# Quasar_ARM.net
KiCad netlist of a schematic drawn in Altium Designer
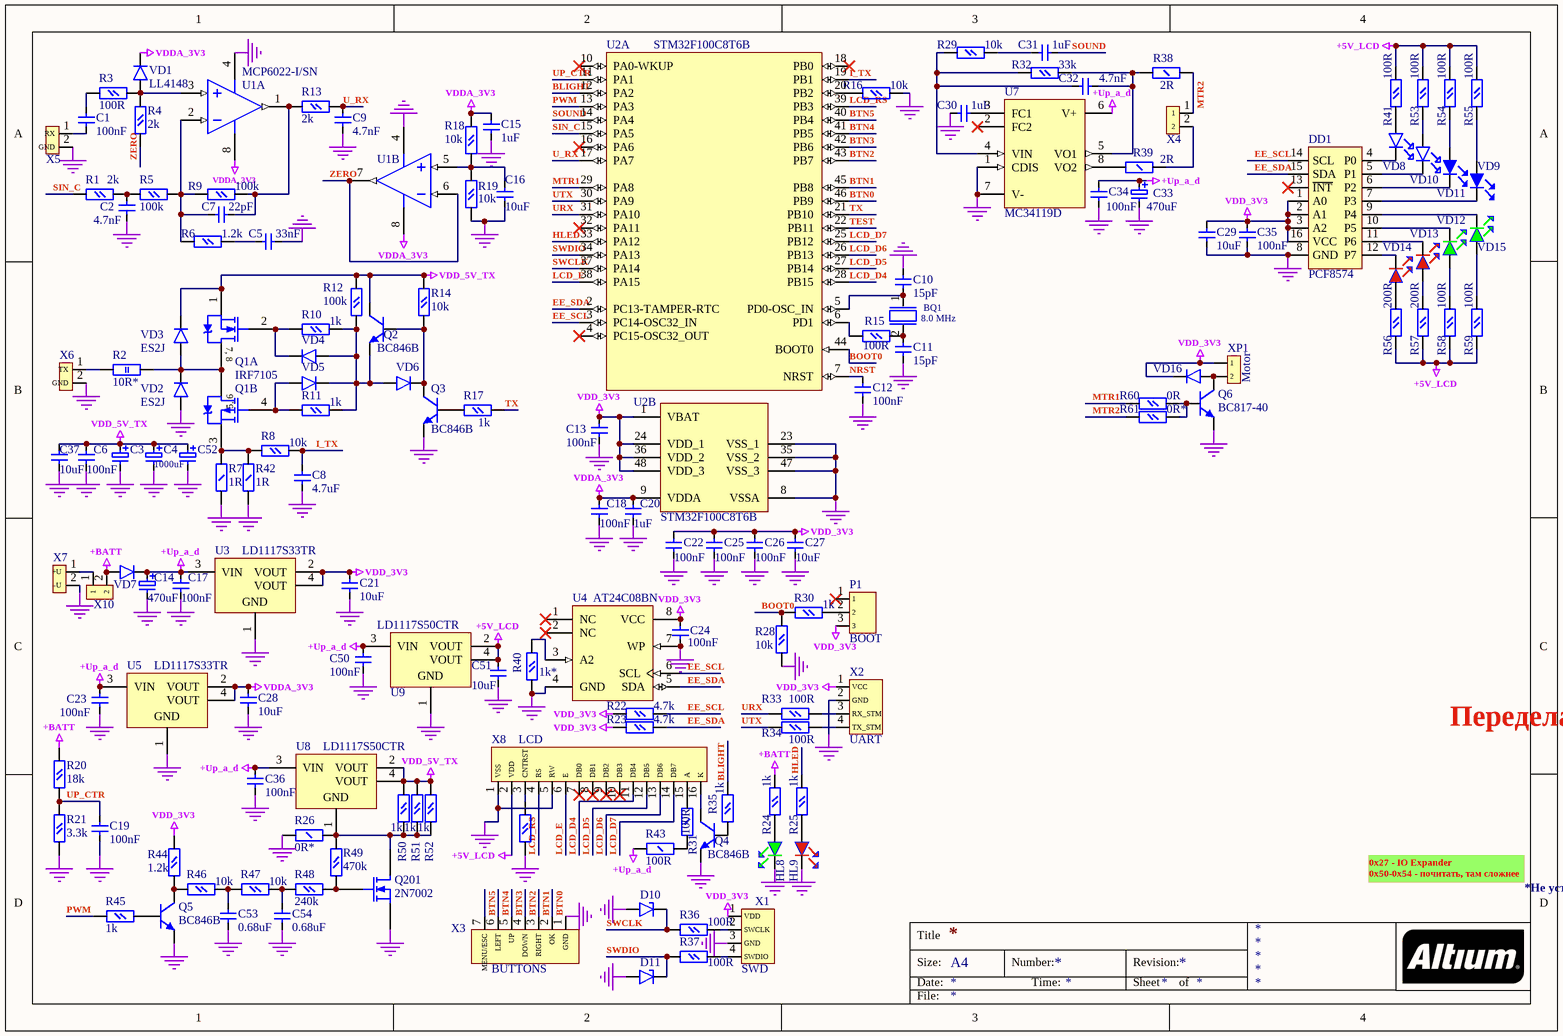
[diagram p0: Quasar_ARM_схема.SchDoc]

(export (version "E")
  (design (tool "Eeschema 10.0.6"))
  (components
    (comp (ref "BQ1")
      (value "8.0 MHz")
      (footprint "Quartz_SMD_2pin")
      (libsource (lib "AS") (part "Quartz_2pin"))
    )
    (comp (ref "C1")
      (value "100nF")
      (footprint "0603_CAP_0.9_CL10A")
      (description "Capacitor_0603")
      (libsource (lib "AS") (part "CAP_0603"))
    )
    (comp (ref "C2")
      (value "4.7nF")
      (footprint "0603_CAP_0.9_CL10A")
      (description "Capacitor_0603")
      (libsource (lib "AS") (part "CAP_0603"))
    )
    (comp (ref "C3")
      (value "1000uF")
      (footprint "CAP-D")
      (description "Capacitor case D")
      (libsource (lib "AS") (part "CAP_D"))
    )
    (comp (ref "C4")
      (value "1000uF")
      (footprint "CAP-D")
      (description "Capacitor case D")
      (libsource (lib "AS") (part "CAP_D"))
    )
    (comp (ref "C5")
      (value "33nF")
      (footprint "0603_CAP_0.9_CL10A")
      (description "Capacitor_0603")
      (libsource (lib "AS") (part "CAP_0603"))
    )
    (comp (ref "C6")
      (value "100nF")
      (footprint "0603_CAP_0.9_CL10A")
      (description "Capacitor_0603")
      (libsource (lib "AS") (part "CAP_0603"))
    )
    (comp (ref "C7")
      (value "22pF")
      (footprint "0603_CAP_0.9_CL10A")
      (description "Capacitor_0603")
      (libsource (lib "AS") (part "CAP_0603"))
    )
    (comp (ref "C8")
      (value "4.7uF")
      (footprint "0603_CAP_0.9_CL10A")
      (description "Capacitor_0603")
      (libsource (lib "AS") (part "CAP_0603"))
    )
    (comp (ref "C9")
      (value "4.7nF")
      (footprint "0603_CAP_0.9_CL10A")
      (description "Capacitor_0603")
      (libsource (lib "AS") (part "CAP_0603"))
    )
    (comp (ref "C10")
      (value "15pF")
      (footprint "0603_CAP_0.9_CL10A")
      (description "Capacitor_0603")
      (libsource (lib "AS") (part "CAP_0603"))
    )
    (comp (ref "C11")
      (value "15pF")
      (footprint "0603_CAP_0.9_CL10A")
      (description "Capacitor_0603")
      (libsource (lib "AS") (part "CAP_0603"))
    )
    (comp (ref "C12")
      (value "100nF")
      (footprint "0603_CAP_0.9_CL10A")
      (description "Capacitor_0603")
      (libsource (lib "AS") (part "CAP_0603"))
    )
    (comp (ref "C13")
      (value "100nF")
      (footprint "0603_CAP_0.9_CL10A")
      (description "Capacitor_0603")
      (libsource (lib "AS") (part "CAP_0603"))
    )
    (comp (ref "C14")
      (value "470uF")
      (footprint "CAP-D")
      (description "Capacitor case D")
      (libsource (lib "AS") (part "CAP_D"))
    )
    (comp (ref "C15")
      (value "1uF")
      (footprint "0603_CAP_0.9_CL10A")
      (description "Capacitor_0603")
      (libsource (lib "AS") (part "CAP_0603"))
    )
    (comp (ref "C16")
      (value "10uF")
      (footprint "1206_C_1.8_CL31B")
      (description "Capacitor_1206")
      (libsource (lib "AS") (part "CAP_1206"))
    )
    (comp (ref "C17")
      (value "100nF")
      (footprint "0603_CAP_0.9_CL10A")
      (description "Capacitor_0603")
      (libsource (lib "AS") (part "CAP_0603"))
    )
    (comp (ref "C18")
      (value "100nF")
      (footprint "0603_CAP_0.9_CL10A")
      (description "Capacitor_0603")
      (libsource (lib "AS") (part "CAP_0603"))
    )
    (comp (ref "C19")
      (value "100nF")
      (footprint "0603_CAP_0.9_CL10A")
      (description "Capacitor_0603")
      (libsource (lib "AS") (part "CAP_0603"))
    )
    (comp (ref "C20")
      (value "1uF")
      (footprint "0603_CAP_0.9_CL10A")
      (description "Capacitor_0603")
      (libsource (lib "AS") (part "CAP_0603"))
    )
    (comp (ref "C21")
      (value "10uF")
      (footprint "1206_C_1.8_CL31B")
      (description "Capacitor_1206")
      (libsource (lib "AS") (part "CAP_1206"))
    )
    (comp (ref "C22")
      (value "100nF")
      (footprint "0603_CAP_0.9_CL10A")
      (description "Capacitor_0603")
      (libsource (lib "AS") (part "CAP_0603"))
    )
    (comp (ref "C23")
      (value "100nF")
      (footprint "0603_CAP_0.9_CL10A")
      (description "Capacitor_0603")
      (libsource (lib "AS") (part "CAP_0603"))
    )
    (comp (ref "C24")
      (value "100nF")
      (footprint "0603_CAP_0.9_CL10A")
      (description "Capacitor_0603")
      (libsource (lib "AS") (part "CAP_0603"))
    )
    (comp (ref "C25")
      (value "100nF")
      (footprint "0603_CAP_0.9_CL10A")
      (description "Capacitor_0603")
      (libsource (lib "AS") (part "CAP_0603"))
    )
    (comp (ref "C26")
      (value "100nF")
      (footprint "0603_CAP_0.9_CL10A")
      (description "Capacitor_0603")
      (libsource (lib "AS") (part "CAP_0603"))
    )
    (comp (ref "C27")
      (value "10uF")
      (footprint "1206_C_1.8_CL31B")
      (description "Capacitor_1206")
      (libsource (lib "AS") (part "CAP_1206"))
    )
    (comp (ref "C28")
      (value "10uF")
      (footprint "1206_C_1.8_CL31B")
      (description "Capacitor_1206")
      (libsource (lib "AS") (part "CAP_1206"))
    )
    (comp (ref "C29")
      (value "10uF")
      (footprint "1206_C_1.8_CL31B")
      (description "Capacitor_1206")
      (libsource (lib "AS") (part "CAP_1206"))
    )
    (comp (ref "C30")
      (value "1uF")
      (footprint "0603_CAP_0.9_CL10A")
      (description "Capacitor_0603")
      (libsource (lib "AS") (part "CAP_0603"))
    )
    (comp (ref "C31")
      (value "1uF")
      (footprint "0603_CAP_0.9_CL10A")
      (description "Capacitor_0603")
      (libsource (lib "AS") (part "CAP_0603"))
    )
    (comp (ref "C32")
      (value "4.7nF")
      (footprint "0603_CAP_0.9_CL10A")
      (description "Capacitor_0603")
      (libsource (lib "AS") (part "CAP_0603"))
    )
    (comp (ref "C33")
      (value "470uF")
      (footprint "CAP-D")
      (description "Capacitor case D")
      (libsource (lib "AS") (part "CAP_D"))
    )
    (comp (ref "C34")
      (value "100nF")
      (footprint "0603_CAP_0.9_CL10A")
      (description "Capacitor_0603")
      (libsource (lib "AS") (part "CAP_0603"))
    )
    (comp (ref "C35")
      (value "100nF")
      (footprint "0603_CAP_0.9_CL10A")
      (description "Capacitor_0603")
      (libsource (lib "AS") (part "CAP_0603"))
    )
    (comp (ref "C36")
      (value "100nF")
      (footprint "0603_CAP_0.9_CL10A")
      (description "Capacitor_0603")
      (libsource (lib "AS") (part "CAP_0603"))
    )
    (comp (ref "C37")
      (value "10uF")
      (footprint "1206_C_1.8_CL31B")
      (description "Capacitor_1206")
      (libsource (lib "AS") (part "CAP_1206"))
    )
    (comp (ref "C50")
      (value "100nF")
      (footprint "0603_CAP_0.9_CL10A")
      (description "Capacitor_0603")
      (libsource (lib "AS") (part "CAP_0603"))
    )
    (comp (ref "C51")
      (value "10uF")
      (footprint "1206_C_1.8_CL31B")
      (description "Capacitor_1206")
      (libsource (lib "AS") (part "CAP_1206"))
    )
    (comp (ref "C52")
      (value "1000uF")
      (footprint "CAP-D")
      (description "Capacitor case D")
      (libsource (lib "AS") (part "CAP_D"))
    )
    (comp (ref "C53")
      (value "0.68uF")
      (footprint "0603_CAP_0.9_CL10A")
      (description "Capacitor_0603")
      (libsource (lib "AS") (part "CAP_0603"))
    )
    (comp (ref "C54")
      (value "0.68uF")
      (footprint "0603_CAP_0.9_CL10A")
      (description "Capacitor_0603")
      (libsource (lib "AS") (part "CAP_0603"))
    )
    (comp (ref "D10")
      (value "BZX384-C5V1")
      (footprint "0402")
      (description "Diode Zener")
      (libsource (lib "AS") (part "Diode_Zener1"))
    )
    (comp (ref "D11")
      (value "BZX384-C5V1")
      (footprint "0402")
      (description "Diode Zener")
      (libsource (lib "AS") (part "Diode_Zener1"))
    )
    (comp (ref "DD1")
      (value "PCF8574")
      (footprint "SOIC127P1030X265-16N")
      (description "I/O Expander")
      (libsource (lib "AS") (part "PCF8574"))
    )
    (comp (ref "HL8")
      (value "GNL-0603GC")
      (footprint "0603")
      (description "0402-0603-1206")
      (libsource (lib "") (part "LED_GREEN_1"))
    )
    (comp (ref "HL9")
      (value "KT-SMD0603-R")
      (footprint "1206")
      (description "0402-0603-1206")
      (libsource (lib "") (part "LED_RED_1"))
    )
    (comp (ref "P1")
      (value "BOOT")
      (footprint "3pin(2.54mm)")
      (libsource (lib "AS") (part "Connector - 3 pin_1"))
    )
    (comp (ref "Q1")
      (value "IRF7105")
      (footprint "SO-8_N")
      (description "HEXFET Power MOSFET")
      (fields (field (name "PUBLISHER") "Altium Limited"))
      (libsource (lib "IR Discrete MOSFET - Power") (part "IRF7105"))
    )
    (comp (ref "Q2")
      (value "BC846B")
      (footprint "SOT-416")
      (description "NPN General-purpose Transistor")
      (libsource (lib "AS") (part "Transistor_NPN"))
    )
    (comp (ref "Q3")
      (value "BC846B")
      (footprint "SOT-416")
      (description "NPN General-purpose Transistor")
      (libsource (lib "AS") (part "Transistor_NPN"))
    )
    (comp (ref "Q4")
      (value "BC846B")
      (footprint "SOT-416")
      (description "NPN General-purpose Transistor")
      (libsource (lib "AS") (part "Transistor_NPN"))
    )
    (comp (ref "Q5")
      (value "BC846B")
      (footprint "SOT-416")
      (description "NPN General-purpose Transistor")
      (libsource (lib "AS") (part "Transistor_NPN"))
    )
    (comp (ref "Q6")
      (value "BC817-40")
      (footprint "SOT-416")
      (description "NPN General-purpose Transistor")
      (libsource (lib "AS") (part "Transistor_NPN"))
    )
    (comp (ref "Q201")
      (value "2N7002")
      (footprint "SOT23")
      (description "N-Channel Enhancement Mode Vertical DMOS FET")
      (fields (field (name "PUBLISHER") "Altium Limited"))
      (libsource (lib "Zetex Discrete MOSFET") (part "2N7002"))
    )
    (comp (ref "R1")
      (value "2k")
      (footprint "0603_R")
      (description "0603")
      (libsource (lib "AS") (part "RES_0603_0.125W"))
    )
    (comp (ref "R2")
      (value "10R*")
      (footprint "R_THT_2W_9x3.2x12.7")
      (description "Res THT")
      (libsource (lib "AS") (part "RES_THT_2W"))
    )
    (comp (ref "R3")
      (value "100R")
      (footprint "0603_R")
      (description "0603")
      (libsource (lib "AS") (part "RES_0603_0.1W"))
    )
    (comp (ref "R4")
      (value "2k")
      (footprint "0603_R")
      (description "0603")
      (libsource (lib "AS") (part "RES_0603_0.125W"))
    )
    (comp (ref "R5")
      (value "100k")
      (footprint "0603_R")
      (description "0603")
      (libsource (lib "AS") (part "RES_0603_0.125W"))
    )
    (comp (ref "R6")
      (value "1.2k")
      (footprint "0603_R")
      (description "0603")
      (libsource (lib "AS") (part "RES_0603_0.125W"))
    )
    (comp (ref "R7")
      (value "1R")
      (footprint "1206_R")
      (description "1206")
      (libsource (lib "AS") (part "RES_1206_0.25W"))
    )
    (comp (ref "R8")
      (value "10k")
      (footprint "0603_R")
      (description "0603")
      (libsource (lib "AS") (part "RES_0603_0.125W"))
    )
    (comp (ref "R9")
      (value "100k")
      (footprint "0603_R")
      (description "0603")
      (libsource (lib "AS") (part "RES_0603_0.125W"))
    )
    (comp (ref "R10")
      (value "1k")
      (footprint "0603_R")
      (description "0603")
      (libsource (lib "AS") (part "RES_0603_0.125W"))
    )
    (comp (ref "R11")
      (value "1k")
      (footprint "0603_R")
      (description "0603")
      (libsource (lib "AS") (part "RES_0603_0.125W"))
    )
    (comp (ref "R12")
      (value "100k")
      (footprint "0603_R")
      (description "0603")
      (libsource (lib "AS") (part "RES_0603_0.125W"))
    )
    (comp (ref "R13")
      (value "2k")
      (footprint "0603_R")
      (description "0603")
      (libsource (lib "AS") (part "RES_0603_0.125W"))
    )
    (comp (ref "R14")
      (value "10k")
      (footprint "0603_R")
      (description "0603")
      (libsource (lib "AS") (part "RES_0603_0.125W"))
    )
    (comp (ref "R15")
      (value "100R")
      (footprint "0603_R")
      (description "0603")
      (libsource (lib "AS") (part "RES_0603_0.1W"))
    )
    (comp (ref "R16")
      (value "10k")
      (footprint "0603_R")
      (description "0603")
      (libsource (lib "AS") (part "RES_0603_0.125W"))
    )
    (comp (ref "R17")
      (value "1k")
      (footprint "0603_R")
      (description "0603")
      (libsource (lib "AS") (part "RES_0603_0.125W"))
    )
    (comp (ref "R18")
      (value "10k")
      (footprint "0603_R")
      (description "0603")
      (libsource (lib "AS") (part "RES_0603_0.125W"))
    )
    (comp (ref "R19")
      (value "10k")
      (footprint "0603_R")
      (description "0603")
      (libsource (lib "AS") (part "RES_0603_0.125W"))
    )
    (comp (ref "R20")
      (value "18k")
      (footprint "0603_R")
      (description "0603")
      (libsource (lib "AS") (part "RES_0603_0.125W"))
    )
    (comp (ref "R21")
      (value "3.3k")
      (footprint "0603_R")
      (description "0603")
      (libsource (lib "AS") (part "RES_0603_0.125W"))
    )
    (comp (ref "R22")
      (value "4.7k")
      (footprint "0603_R")
      (description "0603")
      (libsource (lib "AS") (part "RES_0603_0.125W"))
    )
    (comp (ref "R23")
      (value "4.7k")
      (footprint "0603_R")
      (description "0603")
      (libsource (lib "AS") (part "RES_0603_0.125W"))
    )
    (comp (ref "R24")
      (value "1k")
      (footprint "0603_R")
      (description "0603")
      (libsource (lib "AS") (part "RES_0603_0.125W"))
    )
    (comp (ref "R25")
      (value "1k")
      (footprint "0603_R")
      (description "0603")
      (libsource (lib "AS") (part "RES_0603_0.125W"))
    )
    (comp (ref "R26")
      (value "0R*")
      (footprint "1206_R")
      (description "1206")
      (libsource (lib "AS") (part "RES_1206_0.25W"))
    )
    (comp (ref "R27")
      (value "10k-contrast")
      (footprint "0603_R")
      (description "0603")
      (libsource (lib "AS") (part "RES_0603_0.125W"))
    )
    (comp (ref "R28")
      (value "10k")
      (footprint "0603_R")
      (description "0603")
      (libsource (lib "AS") (part "RES_0603_0.125W"))
    )
    (comp (ref "R29")
      (value "10k")
      (footprint "0603_R")
      (description "0603")
      (libsource (lib "AS") (part "RES_0603_0.125W"))
    )
    (comp (ref "R30")
      (value "1k")
      (footprint "0603_R")
      (description "0603")
      (libsource (lib "AS") (part "RES_0603_0.125W"))
    )
    (comp (ref "R31")
      (value "100R")
      (footprint "1206_R")
      (description "1206")
      (libsource (lib "AS") (part "RES_1206_0.25W"))
    )
    (comp (ref "R32")
      (value "33k")
      (footprint "0603_R")
      (description "0603")
      (libsource (lib "AS") (part "RES_0603_0.125W"))
    )
    (comp (ref "R33")
      (value "100R")
      (footprint "0603_R")
      (description "0603")
      (libsource (lib "AS") (part "RES_0603_0.1W"))
    )
    (comp (ref "R34")
      (value "100R")
      (footprint "0603_R")
      (description "0603")
      (libsource (lib "AS") (part "RES_0603_0.1W"))
    )
    (comp (ref "R35")
      (value "1k")
      (footprint "0603_R")
      (description "0603")
      (libsource (lib "AS") (part "RES_0603_0.125W"))
    )
    (comp (ref "R36")
      (value "100R")
      (footprint "0603_R")
      (description "0603")
      (libsource (lib "AS") (part "RES_0603_0.1W"))
    )
    (comp (ref "R37")
      (value "100R")
      (footprint "0603_R")
      (description "0603")
      (libsource (lib "AS") (part "RES_0603_0.1W"))
    )
    (comp (ref "R38")
      (value "2R")
      (footprint "1206_R")
      (description "1206")
      (libsource (lib "AS") (part "RES_1206_0.25W"))
    )
    (comp (ref "R39")
      (value "2R")
      (footprint "1206_R")
      (description "1206")
      (libsource (lib "AS") (part "RES_1206_0.25W"))
    )
    (comp (ref "R40")
      (value "1k*")
      (footprint "0603_R")
      (description "0603")
      (libsource (lib "AS") (part "RES_0603_0.125W"))
    )
    (comp (ref "R41")
      (value "100R")
      (footprint "0603_R")
      (description "0603")
      (libsource (lib "AS") (part "RES_0603_0.1W"))
    )
    (comp (ref "R42")
      (value "1R")
      (footprint "1206_R")
      (description "1206")
      (libsource (lib "AS") (part "RES_1206_0.25W"))
    )
    (comp (ref "R43")
      (value "100R")
      (footprint "1206_R")
      (description "1206")
      (libsource (lib "AS") (part "RES_1206_0.25W"))
    )
    (comp (ref "R44")
      (value "1.2k")
      (footprint "0603_R")
      (description "0603")
      (libsource (lib "AS") (part "RES_0603_0.125W"))
    )
    (comp (ref "R45")
      (value "1k")
      (footprint "0603_R")
      (description "0603")
      (libsource (lib "AS") (part "RES_0603_0.125W"))
    )
    (comp (ref "R46")
      (value "10k")
      (footprint "0603_R")
      (description "0603")
      (libsource (lib "AS") (part "RES_0603_0.125W"))
    )
    (comp (ref "R47")
      (value "10k")
      (footprint "0603_R")
      (description "0603")
      (libsource (lib "AS") (part "RES_0603_0.125W"))
    )
    (comp (ref "R48")
      (value "240k")
      (footprint "0603_R")
      (description "0603")
      (libsource (lib "AS") (part "RES_0603_0.125W"))
    )
    (comp (ref "R49")
      (value "470k")
      (footprint "0603_R")
      (description "0603")
      (libsource (lib "AS") (part "RES_0603_0.125W"))
    )
    (comp (ref "R50")
      (value "1k")
      (footprint "0603_R")
      (description "0603")
      (libsource (lib "AS") (part "RES_0603_0.125W"))
    )
    (comp (ref "R51")
      (value "1k")
      (footprint "0603_R")
      (description "0603")
      (libsource (lib "AS") (part "RES_0603_0.125W"))
    )
    (comp (ref "R52")
      (value "1k")
      (footprint "0603_R")
      (description "0603")
      (libsource (lib "AS") (part "RES_0603_0.125W"))
    )
    (comp (ref "R53")
      (value "100R")
      (footprint "0603_R")
      (description "0603")
      (libsource (lib "AS") (part "RES_0603_0.1W"))
    )
    (comp (ref "R54")
      (value "100R")
      (footprint "0603_R")
      (description "0603")
      (libsource (lib "AS") (part "RES_0603_0.1W"))
    )
    (comp (ref "R55")
      (value "100R")
      (footprint "0603_R")
      (description "0603")
      (libsource (lib "AS") (part "RES_0603_0.1W"))
    )
    (comp (ref "R56")
      (value "200R")
      (footprint "0603_R")
      (description "0603")
      (libsource (lib "AS") (part "RES_0603_0.1W"))
    )
    (comp (ref "R57")
      (value "200R")
      (footprint "0603_R")
      (description "0603")
      (libsource (lib "AS") (part "RES_0603_0.1W"))
    )
    (comp (ref "R58")
      (value "100R")
      (footprint "0603_R")
      (description "0603")
      (libsource (lib "AS") (part "RES_0603_0.1W"))
    )
    (comp (ref "R59")
      (value "100R")
      (footprint "0603_R")
      (description "0603")
      (libsource (lib "AS") (part "RES_0603_0.1W"))
    )
    (comp (ref "R60")
      (value "0R")
      (footprint "0603_R")
      (description "0603")
      (libsource (lib "AS") (part "RES_0603_0.1W"))
    )
    (comp (ref "R61")
      (value "0R*")
      (footprint "0603_R")
      (description "0603")
      (libsource (lib "AS") (part "RES_0603_0.1W"))
    )
    (comp (ref "U1")
      (value "MCP6022-I/SN")
      (footprint "SOIC-SN8_N")
      (description "Rail-to-Rail Input/Output, 10 MHz Operational Amplifier, 8-Pin SOIC, Industrial Temperature")
      (fields (field (name "PUBLISHER") "Altium Limited"))
      (libsource (lib "Microchip Linear Devices") (part "MCP6022-I/SN"))
    )
    (comp (ref "U2")
      (value "STM32F100C8T6B")
      (footprint "LQFP48_N")
      (libsource (lib "STMicroelectronics STM32 F1") (part "STM32F100C8T6B"))
    )
    (comp (ref "U3")
      (value "LD1117S33TR")
      (footprint "SOT-223_N")
      (description "Fixed Low Drop Positive Voltage Regulator, 3.3V, 4-Pin SOT-223, Tape and Reel")
      (libsource (lib "STMicroelectronics Power Management Linear Regulator") (part "LD1117S33TR"))
    )
    (comp (ref "U4")
      (value "AT24C08BN")
      (footprint "8S1_N")
      (description "8Kbit (1024 x 8), 2-wire Bus Automotive Serial EEPROM with Write Protect, 2.5V, 8-Pin SOIC, Bulk")
      (fields (field (name "PUBLISHER") "Altium Limited"))
      (libsource (lib "Atmel Memory Serial EEPROM") (part "AT24C08BN-SP25-B"))
    )
    (comp (ref "U5")
      (value "LD1117S33TR")
      (footprint "SOT-223_N")
      (description "Fixed Low Drop Positive Voltage Regulator, 3.3V, 4-Pin SOT-223, Tape and Reel")
      (libsource (lib "STMicroelectronics Power Management Linear Regulator") (part "LD1117S33TR"))
    )
    (comp (ref "U7")
      (value "MC34119D")
      (footprint "751-03_N")
      (description "Low-Power Audio Amplifier")
      (fields (field (name "PUBLISHER") "Altium Limited"))
      (libsource (lib "Motorola Amplifier Audio Amplifier") (part "MC34119D"))
    )
    (comp (ref "U8")
      (value "LD1117S50CTR")
      (footprint "SOT-223_N")
      (description "Fixed Low Drop Positive Voltage Regulator, 5V, 4-Pin SOT-223, Tape and Reel")
      (libsource (lib "STMicroelectronics Power Management Linear Regulator") (part "LD1117S50CTR"))
    )
    (comp (ref "U9")
      (value "LD1117S50CTR")
      (footprint "SOT-223_N")
      (description "Fixed Low Drop Positive Voltage Regulator, 5V, 4-Pin SOT-223, Tape and Reel")
      (libsource (lib "STMicroelectronics Power Management Linear Regulator") (part "LD1117S50CTR"))
    )
    (comp (ref "VD1") (value "LL4148") (footprint "SOD-123FL") (libsource (lib "AS") (part "Diode1")))
    (comp (ref "VD2") (value "ES2J") (footprint "SOD-123FL") (libsource (lib "AS") (part "Diode1")))
    (comp (ref "VD3") (value "ES2J") (footprint "SOD-123FL") (libsource (lib "AS") (part "Diode1")))
    (comp (ref "VD4") (value "LL4148") (footprint "SOD-123FL") (libsource (lib "AS") (part "Diode1")))
    (comp (ref "VD5") (value "LL4148") (footprint "SOD-123FL") (libsource (lib "AS") (part "Diode1")))
    (comp (ref "VD6") (value "LL4148") (footprint "SOD-123FL") (libsource (lib "AS") (part "Diode1")))
    (comp (ref "VD7") (value "PMEG4010BEA") (footprint "SOD-123FL") (libsource (lib "AS") (part "Diode1")))
    (comp (ref "VD8")
      (value "GNL-5013UWC/60")
      (footprint "LED_DIP_5mm")
      (description "0402-0603-1206")
      (libsource (lib "AS") (part "LED_WHITE"))
    )
    (comp (ref "VD9")
      (value "GNL-5013UBW-D")
      (footprint "LED_DIP_5mm")
      (description "0402-0603-1206")
      (libsource (lib "AS") (part "LED_BLUE"))
    )
    (comp (ref "VD10")
      (value "GNL-5013UWC/60")
      (footprint "LED_DIP_5mm")
      (description "0402-0603-1206")
      (libsource (lib "AS") (part "LED_WHITE"))
    )
    (comp (ref "VD11")
      (value "GNL-5013UBW-D")
      (footprint "LED_DIP_5mm")
      (description "0402-0603-1206")
      (libsource (lib "AS") (part "LED_BLUE"))
    )
    (comp (ref "VD12")
      (value "GNL-5013PGW-D")
      (footprint "0603")
      (description "0402-0603-1206")
      (libsource (lib "AS") (part "LED_GREEN"))
    )
    (comp (ref "VD13")
      (value "GNL-5013UEW-D")
      (footprint "1206")
      (description "0402-0603-1206")
      (libsource (lib "AS") (part "LED_RED"))
    )
    (comp (ref "VD14")
      (value "GNL-5013UEW-D")
      (footprint "1206")
      (description "0402-0603-1206")
      (libsource (lib "AS") (part "LED_RED"))
    )
    (comp (ref "VD15")
      (value "GNL-5013PGW-D")
      (footprint "0603")
      (description "0402-0603-1206")
      (libsource (lib "AS") (part "LED_GREEN"))
    )
    (comp (ref "VD16") (value "LL4148") (footprint "SOD-123FL") (libsource (lib "AS") (part "Diode1")))
    (comp (ref "X1")
      (value "SWD")
      (footprint "4pin(2.54mm)")
      (libsource (lib "AS") (part "Connector - 4 pin_1"))
    )
    (comp (ref "X2")
      (value "UART")
      (footprint "4pin(2.54mm)")
      (libsource (lib "AS") (part "Connector - 4 pin_1"))
    )
    (comp (ref "X3")
      (value "BUTTONS")
      (footprint "7pin(2.54mm)")
      (libsource (lib "AS") (part "Connector - 7 pin"))
    )
    (comp (ref "X4")
      (value "*")
      (footprint "2pin(2.54mm)")
      (description "Connector 2-pin")
      (libsource (lib "AS") (part "Connector - 2 pin_1"))
    )
    (comp (ref "X5")
      (value "*")
      (footprint "2pin(2.54mm)")
      (description "Connector 2-pin")
      (libsource (lib "AS") (part "Connector - 2 pin_1"))
    )
    (comp (ref "X6")
      (value "*")
      (footprint "2pin(2.54mm)")
      (description "Connector 2-pin")
      (libsource (lib "AS") (part "Connector - 2 pin_1"))
    )
    (comp (ref "X7")
      (value "*")
      (footprint "2pin(2.54mm)")
      (description "Connector 2-pin")
      (libsource (lib "AS") (part "Connector - 2 pin_1"))
    )
    (comp (ref "X8")
      (value "LCD")
      (footprint "16pin(2.54mm)")
      (libsource (lib "AS") (part "Connector - 16 pin"))
    )
    (comp (ref "X10")
      (value "*")
      (footprint "2pin(2.54mm)")
      (description "Connector 2-pin")
      (libsource (lib "") (part "Connector - 2 pin_1_2"))
    )
    (comp (ref "XP1")
      (value "Motor")
      (footprint "2pin(2.54mm)")
      (description "Connector 2-pin")
      (libsource (lib "") (part "Connector - 2 pin_1_1"))
    )
  )
  (nets
    (net (code "1") (name "+5V_LCD") (class "Default")
      (node (ref "C51") (pin "1") (pinfunction "1_1") (pintype "passive"))
      (node (ref "R41") (pin "2") (pinfunction "2_2") (pintype "passive"))
      (node (ref "R53") (pin "2") (pinfunction "2_2") (pintype "passive"))
      (node (ref "R54") (pin "2") (pinfunction "2_2") (pintype "passive"))
      (node (ref "R55") (pin "2") (pinfunction "2_2") (pintype "passive"))
      (node (ref "R56") (pin "1") (pinfunction "1_1") (pintype "passive"))
      (node (ref "R57") (pin "1") (pinfunction "1_1") (pintype "passive"))
      (node (ref "R58") (pin "1") (pinfunction "1_1") (pintype "passive"))
      (node (ref "R59") (pin "1") (pinfunction "1_1") (pintype "passive"))
      (node (ref "U9") (pin "2") (pinfunction "VOUT_2") (pintype "power_in"))
      (node (ref "U9") (pin "4") (pinfunction "VOUT_4") (pintype "power_in"))
      (node (ref "X8") (pin "2") (pinfunction "VDD_2") (pintype "passive"))
    )
    (net (code "2") (name "+BATT") (class "Default")
      (node (ref "R20") (pin "2") (pinfunction "2_2") (pintype "passive"))
      (node (ref "R24") (pin "1") (pinfunction "1_1") (pintype "passive"))
      (node (ref "VD7") (pin "1") (pinfunction "ANODE_1") (pintype "passive"))
      (node (ref "X10") (pin "2") (pinfunction "2_2") (pintype "passive"))
    )
    (net (code "3") (name "+Up_a_d") (class "Default")
      (node (ref "C14") (pin "1") (pinfunction "1_1") (pintype "passive"))
      (node (ref "C17") (pin "1") (pinfunction "1_1") (pintype "passive"))
      (node (ref "C23") (pin "1") (pinfunction "1_1") (pintype "passive"))
      (node (ref "C33") (pin "1") (pinfunction "1_1") (pintype "passive"))
      (node (ref "C34") (pin "1") (pinfunction "1_1") (pintype "passive"))
      (node (ref "C36") (pin "1") (pinfunction "1_1") (pintype "passive"))
      (node (ref "C50") (pin "1") (pinfunction "1_1") (pintype "passive"))
      (node (ref "R43") (pin "2") (pinfunction "2_2") (pintype "passive"))
      (node (ref "U3") (pin "3") (pinfunction "VIN_3") (pintype "power_in"))
      (node (ref "U5") (pin "3") (pinfunction "VIN_3") (pintype "power_in"))
      (node (ref "U7") (pin "6") (pinfunction "V+_6") (pintype "power_in"))
      (node (ref "U8") (pin "3") (pinfunction "VIN_3") (pintype "power_in"))
      (node (ref "U9") (pin "3") (pinfunction "VIN_3") (pintype "power_in"))
      (node (ref "VD7") (pin "2") (pinfunction "CATODE1_2") (pintype "passive"))
    )
    (net (code "4") (name "/BLIGHT") (class "Default")
      (node (ref "R35") (pin "1") (pinfunction "1_1") (pintype "passive"))
      (node (ref "U2") (pin "12") (pinfunction "PA2_12") (pintype "bidirectional"))
    )
    (net (code "5") (name "/BOOT0") (class "Default")
      (node (ref "R28") (pin "1") (pinfunction "1_1") (pintype "passive"))
      (node (ref "R30") (pin "2") (pinfunction "2_2") (pintype "passive"))
      (node (ref "U2") (pin "44") (pinfunction "BOOT0_44") (pintype "input"))
    )
    (net (code "6") (name "/BTN0") (class "Default")
      (node (ref "U2") (pin "46") (pinfunction "PB9_46") (pintype "bidirectional"))
      (node (ref "X3") (pin "2") (pinfunction "OK_2") (pintype "passive"))
    )
    (net (code "7") (name "/BTN1") (class "Default")
      (node (ref "U2") (pin "45") (pinfunction "PB8_45") (pintype "bidirectional"))
      (node (ref "X3") (pin "3") (pinfunction "RIGHT_3") (pintype "passive"))
    )
    (net (code "8") (name "/BTN2") (class "Default")
      (node (ref "U2") (pin "43") (pinfunction "PB7_43") (pintype "bidirectional"))
      (node (ref "X3") (pin "4") (pinfunction "DOWN_4") (pintype "passive"))
    )
    (net (code "9") (name "/BTN3") (class "Default")
      (node (ref "U2") (pin "42") (pinfunction "PB6_42") (pintype "bidirectional"))
      (node (ref "X3") (pin "5") (pinfunction "UP_5") (pintype "passive"))
    )
    (net (code "10") (name "/BTN4") (class "Default")
      (node (ref "U2") (pin "41") (pinfunction "PB5_41") (pintype "bidirectional"))
      (node (ref "X3") (pin "6") (pinfunction "LEFT_6") (pintype "passive"))
    )
    (net (code "11") (name "/BTN5") (class "Default")
      (node (ref "U2") (pin "40") (pinfunction "PB4_40") (pintype "bidirectional"))
      (node (ref "X3") (pin "7") (pinfunction "MENU/ESC_7") (pintype "passive"))
    )
    (net (code "12") (name "/EE_SCL") (class "Default")
      (node (ref "DD1") (pin "14") (pinfunction "SCL_14") (pintype "passive"))
      (node (ref "R22") (pin "1") (pinfunction "1_1") (pintype "passive"))
      (node (ref "U2") (pin "3") (pinfunction "PC14-OSC32_IN_3") (pintype "bidirectional"))
      (node (ref "U4") (pin "6") (pinfunction "SCL_6") (pintype "input"))
    )
    (net (code "13") (name "/EE_SDA") (class "Default")
      (node (ref "DD1") (pin "15") (pinfunction "SDA_15") (pintype "passive"))
      (node (ref "R23") (pin "1") (pinfunction "1_1") (pintype "passive"))
      (node (ref "U2") (pin "2") (pinfunction "PC13-TAMPER-RTC_2") (pintype "bidirectional"))
      (node (ref "U4") (pin "5") (pinfunction "SDA_5") (pintype "bidirectional"))
    )
    (net (code "14") (name "/HLED") (class "Default")
      (node (ref "R25") (pin "1") (pinfunction "1_1") (pintype "passive"))
      (node (ref "U2") (pin "33") (pinfunction "PA12_33") (pintype "bidirectional"))
    )
    (net (code "15") (name "/I_TX") (class "Default")
      (node (ref "C8") (pin "1") (pinfunction "1_1") (pintype "passive"))
      (node (ref "R8") (pin "1") (pinfunction "1_1") (pintype "passive"))
      (node (ref "U2") (pin "19") (pinfunction "PB1_19") (pintype "bidirectional"))
    )
    (net (code "16") (name "/LCD_D4") (class "Default")
      (node (ref "U2") (pin "28") (pinfunction "PB15_28") (pintype "bidirectional"))
      (node (ref "X8") (pin "11") (pinfunction "DB4_11") (pintype "passive"))
    )
    (net (code "17") (name "/LCD_D5") (class "Default")
      (node (ref "U2") (pin "27") (pinfunction "PB14_27") (pintype "bidirectional"))
      (node (ref "X8") (pin "12") (pinfunction "DB5_12") (pintype "passive"))
    )
    (net (code "18") (name "/LCD_D6") (class "Default")
      (node (ref "U2") (pin "26") (pinfunction "PB13_26") (pintype "bidirectional"))
      (node (ref "X8") (pin "13") (pinfunction "DB6_13") (pintype "passive"))
    )
    (net (code "19") (name "/LCD_D7") (class "Default")
      (node (ref "U2") (pin "25") (pinfunction "PB12_25") (pintype "bidirectional"))
      (node (ref "X8") (pin "14") (pinfunction "DB7_14") (pintype "passive"))
    )
    (net (code "20") (name "/LCD_E") (class "Default")
      (node (ref "U2") (pin "38") (pinfunction "PA15_38") (pintype "bidirectional"))
      (node (ref "X8") (pin "6") (pinfunction "E_6") (pintype "passive"))
    )
    (net (code "21") (name "/LCD_RS") (class "Default")
      (node (ref "U2") (pin "39") (pinfunction "PB3_39") (pintype "bidirectional"))
      (node (ref "X8") (pin "4") (pinfunction "RS_4") (pintype "passive"))
    )
    (net (code "22") (name "/MTR1") (class "Default")
      (node (ref "R60") (pin "2") (pinfunction "2_2") (pintype "passive"))
      (node (ref "U2") (pin "29") (pinfunction "PA8_29") (pintype "bidirectional"))
    )
    (net (code "23") (name "/MTR2") (class "Default")
      (node (ref "R38") (pin "2") (pinfunction "2_2") (pintype "passive"))
      (node (ref "R61") (pin "2") (pinfunction "2_2") (pintype "passive"))
      (node (ref "X4") (pin "1") (pinfunction "RX_1") (pintype "passive"))
    )
    (net (code "24") (name "/NRST") (class "Default")
      (node (ref "C12") (pin "1") (pinfunction "1_1") (pintype "passive"))
      (node (ref "U2") (pin "7") (pinfunction "NRST_7") (pintype "bidirectional"))
    )
    (net (code "25") (name "/PWM") (class "Default")
      (node (ref "R45") (pin "1") (pinfunction "1_1") (pintype "passive"))
      (node (ref "U2") (pin "13") (pinfunction "PA3_13") (pintype "bidirectional"))
    )
    (net (code "26") (name "/SIN_C") (class "Default")
      (node (ref "R1") (pin "2") (pinfunction "2_2") (pintype "passive"))
      (node (ref "U2") (pin "15") (pinfunction "PA5_15") (pintype "bidirectional"))
    )
    (net (code "27") (name "/SOUND") (class "Default")
      (node (ref "C31") (pin "2") (pinfunction "2_2") (pintype "passive"))
      (node (ref "U2") (pin "14") (pinfunction "PA4_14") (pintype "bidirectional"))
    )
    (net (code "28") (name "/SWCLK") (class "Default")
      (node (ref "D10") (pin "1") (pinfunction "CATODE_1") (pintype "passive"))
      (node (ref "R36") (pin "2") (pinfunction "2_2") (pintype "passive"))
      (node (ref "U2") (pin "37") (pinfunction "PA14_37") (pintype "bidirectional"))
    )
    (net (code "29") (name "/SWDIO") (class "Default")
      (node (ref "D11") (pin "1") (pinfunction "CATODE_1") (pintype "passive"))
      (node (ref "R37") (pin "2") (pinfunction "2_2") (pintype "passive"))
      (node (ref "U2") (pin "34") (pinfunction "PA13_34") (pintype "bidirectional"))
    )
    (net (code "30") (name "/TEST") (class "Default")
      (node (ref "U2") (pin "22") (pinfunction "PB11_22") (pintype "bidirectional"))
    )
    (net (code "31") (name "/TX") (class "Default")
      (node (ref "R17") (pin "2") (pinfunction "2_2") (pintype "passive"))
      (node (ref "U2") (pin "21") (pinfunction "PB10_21") (pintype "bidirectional"))
    )
    (net (code "32") (name "/UP_CTR") (class "Default")
      (node (ref "C19") (pin "1") (pinfunction "1_1") (pintype "passive"))
      (node (ref "R20") (pin "1") (pinfunction "1_1") (pintype "passive"))
      (node (ref "R21") (pin "2") (pinfunction "2_2") (pintype "passive"))
      (node (ref "U2") (pin "11") (pinfunction "PA1_11") (pintype "bidirectional"))
    )
    (net (code "33") (name "/URX") (class "Default")
      (node (ref "R33") (pin "1") (pinfunction "1_1") (pintype "passive"))
      (node (ref "U2") (pin "31") (pinfunction "PA10_31") (pintype "bidirectional"))
    )
    (net (code "34") (name "/UTX") (class "Default")
      (node (ref "R34") (pin "2") (pinfunction "2_2") (pintype "passive"))
      (node (ref "U2") (pin "30") (pinfunction "PA9_30") (pintype "bidirectional"))
    )
    (net (code "35") (name "/U_RX") (class "Default")
      (node (ref "C9") (pin "2") (pinfunction "2_2") (pintype "passive"))
      (node (ref "R13") (pin "2") (pinfunction "2_2") (pintype "passive"))
      (node (ref "U2") (pin "17") (pinfunction "PA7_17") (pintype "bidirectional"))
    )
    (net (code "36") (name "/ZERO") (class "Default")
      (node (ref "R4") (pin "2") (pinfunction "2_2") (pintype "passive"))
      (node (ref "U1") (pin "6") (pinfunction "VINB-_6") (pintype "input"))
      (node (ref "U1") (pin "7") (pinfunction "VOUTB_7") (pintype "output"))
    )
    (net (code "37") (name "GND") (class "Default")
      (node (ref "C10") (pin "1") (pinfunction "1_1") (pintype "passive"))
      (node (ref "C11") (pin "2") (pinfunction "2_2") (pintype "passive"))
      (node (ref "C12") (pin "2") (pinfunction "2_2") (pintype "passive"))
      (node (ref "C13") (pin "2") (pinfunction "2_2") (pintype "passive"))
      (node (ref "C14") (pin "2") (pinfunction "2_2") (pintype "passive"))
      (node (ref "C15") (pin "1") (pinfunction "1_1") (pintype "passive"))
      (node (ref "C16") (pin "2") (pinfunction "2_2") (pintype "passive"))
      (node (ref "C17") (pin "2") (pinfunction "2_2") (pintype "passive"))
      (node (ref "C18") (pin "2") (pinfunction "2_2") (pintype "passive"))
      (node (ref "C19") (pin "2") (pinfunction "2_2") (pintype "passive"))
      (node (ref "C2") (pin "1") (pinfunction "1_1") (pintype "passive"))
      (node (ref "C20") (pin "1") (pinfunction "1_1") (pintype "passive"))
      (node (ref "C21") (pin "2") (pinfunction "2_2") (pintype "passive"))
      (node (ref "C22") (pin "2") (pinfunction "2_2") (pintype "passive"))
      (node (ref "C23") (pin "2") (pinfunction "2_2") (pintype "passive"))
      (node (ref "C24") (pin "2") (pinfunction "2_2") (pintype "passive"))
      (node (ref "C25") (pin "2") (pinfunction "2_2") (pintype "passive"))
      (node (ref "C26") (pin "2") (pinfunction "2_2") (pintype "passive"))
      (node (ref "C27") (pin "2") (pinfunction "2_2") (pintype "passive"))
      (node (ref "C28") (pin "2") (pinfunction "2_2") (pintype "passive"))
      (node (ref "C29") (pin "2") (pinfunction "2_2") (pintype "passive"))
      (node (ref "C3") (pin "2") (pinfunction "2_2") (pintype "passive"))
      (node (ref "C30") (pin "1") (pinfunction "1_1") (pintype "passive"))
      (node (ref "C33") (pin "2") (pinfunction "2_2") (pintype "passive"))
      (node (ref "C34") (pin "2") (pinfunction "2_2") (pintype "passive"))
      (node (ref "C35") (pin "2") (pinfunction "2_2") (pintype "passive"))
      (node (ref "C36") (pin "2") (pinfunction "2_2") (pintype "passive"))
      (node (ref "C37") (pin "2") (pinfunction "2_2") (pintype "passive"))
      (node (ref "C4") (pin "2") (pinfunction "2_2") (pintype "passive"))
      (node (ref "C5") (pin "1") (pinfunction "1_1") (pintype "passive"))
      (node (ref "C50") (pin "2") (pinfunction "2_2") (pintype "passive"))
      (node (ref "C51") (pin "2") (pinfunction "2_2") (pintype "passive"))
      (node (ref "C52") (pin "2") (pinfunction "2_2") (pintype "passive"))
      (node (ref "C53") (pin "2") (pinfunction "2_2") (pintype "passive"))
      (node (ref "C54") (pin "2") (pinfunction "2_2") (pintype "passive"))
      (node (ref "C6") (pin "1") (pinfunction "1_1") (pintype "passive"))
      (node (ref "C8") (pin "2") (pinfunction "2_2") (pintype "passive"))
      (node (ref "C9") (pin "1") (pinfunction "1_1") (pintype "passive"))
      (node (ref "D10") (pin "2") (pinfunction "ANODE_2") (pintype "passive"))
      (node (ref "D11") (pin "2") (pinfunction "ANODE_2") (pintype "passive"))
      (node (ref "DD1") (pin "8") (pinfunction "GND_8") (pintype "passive"))
      (node (ref "HL8") (pin "2") (pinfunction "CATODE1_2") (pintype "passive"))
      (node (ref "HL9") (pin "2") (pinfunction "CATODE1_2") (pintype "passive"))
      (node (ref "Q201") (pin "2") (pinfunction "S_2") (pintype "passive"))
      (node (ref "Q3") (pin "2") (pinfunction "E_2") (pintype "passive"))
      (node (ref "Q4") (pin "2") (pinfunction "E_2") (pintype "passive"))
      (node (ref "Q5") (pin "2") (pinfunction "E_2") (pintype "passive"))
      (node (ref "Q6") (pin "2") (pinfunction "E_2") (pintype "passive"))
      (node (ref "R16") (pin "1") (pinfunction "1_1") (pintype "passive"))
      (node (ref "R19") (pin "2") (pinfunction "2_2") (pintype "passive"))
      (node (ref "R21") (pin "1") (pinfunction "1_1") (pintype "passive"))
      (node (ref "R26") (pin "1") (pinfunction "1_1") (pintype "passive"))
      (node (ref "R27") (pin "2") (pinfunction "2_2") (pintype "passive"))
      (node (ref "R28") (pin "2") (pinfunction "2_2") (pintype "passive"))
      (node (ref "R40") (pin "2") (pinfunction "2_2") (pintype "passive"))
      (node (ref "R42") (pin "2") (pinfunction "2_2") (pintype "passive"))
      (node (ref "R7") (pin "2") (pinfunction "2_2") (pintype "passive"))
      (node (ref "U1") (pin "4") (pinfunction "VSS_4") (pintype "power_in"))
      (node (ref "U2") (pin "23") (pinfunction "VSS_1_23") (pintype "power_in"))
      (node (ref "U2") (pin "35") (pinfunction "VSS_2_35") (pintype "power_in"))
      (node (ref "U2") (pin "47") (pinfunction "VSS_3_47") (pintype "power_in"))
      (node (ref "U2") (pin "8") (pinfunction "VSSA_8") (pintype "power_in"))
      (node (ref "U3") (pin "1") (pinfunction "GND_1") (pintype "power_in"))
      (node (ref "U4") (pin "4") (pinfunction "GND_4") (pintype "power_in"))
      (node (ref "U4") (pin "7") (pinfunction "WP_7") (pintype "input"))
      (node (ref "U5") (pin "1") (pinfunction "GND_1") (pintype "power_in"))
      (node (ref "U7") (pin "1") (pinfunction "CDIS_1") (pintype "input"))
      (node (ref "U7") (pin "7") (pinfunction "V-_7") (pintype "power_in"))
      (node (ref "U9") (pin "1") (pinfunction "GND_1") (pintype "power_in"))
      (node (ref "VD2") (pin "1") (pinfunction "ANODE_1") (pintype "passive"))
      (node (ref "X1") (pin "3") (pinfunction "GND_3") (pintype "passive"))
      (node (ref "X2") (pin "2") (pinfunction "SWCLK_2") (pintype "passive"))
      (node (ref "X3") (pin "1") (pinfunction "GND_1") (pintype "passive"))
      (node (ref "X5") (pin "2") (pinfunction "GND_2") (pintype "passive"))
      (node (ref "X6") (pin "2") (pinfunction "GND_2") (pintype "passive"))
      (node (ref "X7") (pin "2") (pinfunction "GND_2") (pintype "passive"))
      (node (ref "X8") (pin "1") (pinfunction "VSS_1") (pintype "passive"))
      (node (ref "X8") (pin "5") (pinfunction "RW_5") (pintype "passive"))
    )
    (net (code "38") (name "Net-(BQ1-Pad2)") (class "Default")
      (node (ref "BQ1") (pin "2") (pinfunction "2_2") (pintype "passive"))
      (node (ref "C11") (pin "1") (pinfunction "1_1") (pintype "passive"))
      (node (ref "R15") (pin "2") (pinfunction "2_2") (pintype "passive"))
    )
    (net (code "39") (name "Net-(C1-Pad1)") (class "Default")
      (node (ref "C1") (pin "1") (pinfunction "1_1") (pintype "passive"))
      (node (ref "R3") (pin "2") (pinfunction "2_2") (pintype "passive"))
    )
    (net (code "40") (name "Net-(C2-Pad2)") (class "Default")
      (node (ref "C2") (pin "2") (pinfunction "2_2") (pintype "passive"))
      (node (ref "R1") (pin "1") (pinfunction "1_1") (pintype "passive"))
      (node (ref "R5") (pin "2") (pinfunction "2_2") (pintype "passive"))
    )
    (net (code "41") (name "Net-(C5-Pad2)") (class "Default")
      (node (ref "C5") (pin "2") (pinfunction "2_2") (pintype "passive"))
      (node (ref "R6") (pin "2") (pinfunction "2_2") (pintype "passive"))
    )
    (net (code "42") (name "Net-(C31-Pad1)") (class "Default")
      (node (ref "C31") (pin "1") (pinfunction "1_1") (pintype "passive"))
      (node (ref "R29") (pin "2") (pinfunction "2_2") (pintype "passive"))
    )
    (net (code "43") (name "Net-(C53-Pad1)") (class "Default")
      (node (ref "C53") (pin "1") (pinfunction "1_1") (pintype "passive"))
      (node (ref "R46") (pin "2") (pinfunction "2_2") (pintype "passive"))
      (node (ref "R47") (pin "1") (pinfunction "1_1") (pintype "passive"))
    )
    (net (code "44") (name "Net-(C54-Pad1)") (class "Default")
      (node (ref "C54") (pin "1") (pinfunction "1_1") (pintype "passive"))
      (node (ref "R47") (pin "2") (pinfunction "2_2") (pintype "passive"))
      (node (ref "R48") (pin "2") (pinfunction "2_2") (pintype "passive"))
    )
    (net (code "45") (name "Net-(DD1-P0)") (class "Default")
      (node (ref "DD1") (pin "4") (pinfunction "P0_4") (pintype "passive"))
      (node (ref "VD8") (pin "1") (pinfunction "CATODE_1") (pintype "passive"))
    )
    (net (code "46") (name "Net-(DD1-P1)") (class "Default")
      (node (ref "DD1") (pin "5") (pinfunction "P1_5") (pintype "passive"))
      (node (ref "VD10") (pin "1") (pinfunction "CATODE_1") (pintype "passive"))
    )
    (net (code "47") (name "Net-(DD1-P2)") (class "Default")
      (node (ref "DD1") (pin "6") (pinfunction "P2_6") (pintype "passive"))
      (node (ref "VD11") (pin "1") (pinfunction "CATODE_1") (pintype "passive"))
    )
    (net (code "48") (name "Net-(DD1-P3)") (class "Default")
      (node (ref "DD1") (pin "7") (pinfunction "P3_7") (pintype "passive"))
      (node (ref "VD9") (pin "1") (pinfunction "CATODE_1") (pintype "passive"))
    )
    (net (code "49") (name "Net-(DD1-P4)") (class "Default")
      (node (ref "DD1") (pin "9") (pinfunction "P4_9") (pintype "passive"))
      (node (ref "VD15") (pin "1") (pinfunction "CATODE_1") (pintype "passive"))
    )
    (net (code "50") (name "Net-(DD1-P5)") (class "Default")
      (node (ref "DD1") (pin "10") (pinfunction "P5_10") (pintype "passive"))
      (node (ref "VD12") (pin "1") (pinfunction "CATODE_1") (pintype "passive"))
    )
    (net (code "51") (name "Net-(DD1-P6)") (class "Default")
      (node (ref "DD1") (pin "11") (pinfunction "P6_11") (pintype "passive"))
      (node (ref "VD13") (pin "1") (pinfunction "CATODE_1") (pintype "passive"))
    )
    (net (code "52") (name "Net-(DD1-P7)") (class "Default")
      (node (ref "DD1") (pin "12") (pinfunction "P7_12") (pintype "passive"))
      (node (ref "VD14") (pin "1") (pinfunction "CATODE_1") (pintype "passive"))
    )
    (net (code "53") (name "Net-(HL8-ANODE)") (class "Default")
      (node (ref "HL8") (pin "1") (pinfunction "ANODE_1") (pintype "passive"))
      (node (ref "R24") (pin "2") (pinfunction "2_2") (pintype "passive"))
    )
    (net (code "54") (name "Net-(HL9-ANODE)") (class "Default")
      (node (ref "HL9") (pin "1") (pinfunction "ANODE_1") (pintype "passive"))
      (node (ref "R25") (pin "2") (pinfunction "2_2") (pintype "passive"))
    )
    (net (code "55") (name "Net-(P1-Pad2)") (class "Default")
      (node (ref "P1") (pin "2") (pinfunction "2_2") (pintype "passive"))
      (node (ref "R30") (pin "1") (pinfunction "1_1") (pintype "passive"))
    )
    (net (code "56") (name "Net-(Q1A-G1)") (class "Default")
      (node (ref "Q1") (pin "2") (pinfunction "G1_2") (pintype "passive"))
      (node (ref "R10") (pin "2") (pinfunction "2_2") (pintype "passive"))
      (node (ref "VD4") (pin "2") (pinfunction "CATODE1_2") (pintype "passive"))
    )
    (net (code "57") (name "Net-(Q1B-G2)") (class "Default")
      (node (ref "Q1") (pin "4") (pinfunction "G2_4") (pintype "passive"))
      (node (ref "R11") (pin "2") (pinfunction "2_2") (pintype "passive"))
      (node (ref "VD5") (pin "1") (pinfunction "ANODE_1") (pintype "passive"))
    )
    (net (code "58") (name "Net-(Q1B-S2)") (class "Default")
      (node (ref "Q1") (pin "3") (pinfunction "S2_3") (pintype "passive"))
      (node (ref "R42") (pin "1") (pinfunction "1_1") (pintype "passive"))
      (node (ref "R7") (pin "1") (pinfunction "1_1") (pintype "passive"))
      (node (ref "R8") (pin "2") (pinfunction "2_2") (pintype "passive"))
    )
    (net (code "59") (name "Net-(Q2-B)") (class "Default")
      (node (ref "Q2") (pin "1") (pinfunction "B_1") (pintype "passive"))
      (node (ref "Q3") (pin "3") (pinfunction "C_3") (pintype "passive"))
      (node (ref "R14") (pin "2") (pinfunction "2_2") (pintype "passive"))
      (node (ref "VD6") (pin "2") (pinfunction "CATODE1_2") (pintype "passive"))
    )
    (net (code "60") (name "Net-(Q2-E)") (class "Default")
      (node (ref "Q2") (pin "2") (pinfunction "E_2") (pintype "passive"))
      (node (ref "R10") (pin "1") (pinfunction "1_1") (pintype "passive"))
      (node (ref "R11") (pin "1") (pinfunction "1_1") (pintype "passive"))
      (node (ref "R12") (pin "2") (pinfunction "2_2") (pintype "passive"))
      (node (ref "VD4") (pin "1") (pinfunction "ANODE_1") (pintype "passive"))
      (node (ref "VD5") (pin "2") (pinfunction "CATODE1_2") (pintype "passive"))
      (node (ref "VD6") (pin "1") (pinfunction "ANODE_1") (pintype "passive"))
    )
    (net (code "61") (name "Net-(Q3-B)") (class "Default")
      (node (ref "Q3") (pin "1") (pinfunction "B_1") (pintype "passive"))
      (node (ref "R17") (pin "1") (pinfunction "1_1") (pintype "passive"))
    )
    (net (code "62") (name "Net-(Q4-B)") (class "Default")
      (node (ref "Q4") (pin "1") (pinfunction "B_1") (pintype "passive"))
      (node (ref "R35") (pin "2") (pinfunction "2_2") (pintype "passive"))
    )
    (net (code "63") (name "Net-(Q4-C)") (class "Default")
      (node (ref "Q4") (pin "3") (pinfunction "C_3") (pintype "passive"))
      (node (ref "X8") (pin "16") (pinfunction "K_16") (pintype "passive"))
    )
    (net (code "64") (name "Net-(Q5-B)") (class "Default")
      (node (ref "Q5") (pin "1") (pinfunction "B_1") (pintype "passive"))
      (node (ref "R45") (pin "2") (pinfunction "2_2") (pintype "passive"))
    )
    (net (code "65") (name "Net-(Q5-C)") (class "Default")
      (node (ref "Q5") (pin "3") (pinfunction "C_3") (pintype "passive"))
      (node (ref "R44") (pin "1") (pinfunction "1_1") (pintype "passive"))
      (node (ref "R46") (pin "1") (pinfunction "1_1") (pintype "passive"))
    )
    (net (code "66") (name "Net-(Q6-B)") (class "Default")
      (node (ref "Q6") (pin "1") (pinfunction "B_1") (pintype "passive"))
      (node (ref "R60") (pin "1") (pinfunction "1_1") (pintype "passive"))
      (node (ref "R61") (pin "1") (pinfunction "1_1") (pintype "passive"))
    )
    (net (code "67") (name "Net-(Q6-C)") (class "Default")
      (node (ref "Q6") (pin "3") (pinfunction "C_3") (pintype "passive"))
      (node (ref "VD16") (pin "1") (pinfunction "ANODE_1") (pintype "passive"))
      (node (ref "XP1") (pin "2") (pinfunction "2_2") (pintype "passive"))
    )
    (net (code "68") (name "Net-(Q201-D)") (class "Default")
      (node (ref "Q201") (pin "1") (pinfunction "D_1") (pintype "passive"))
      (node (ref "R26") (pin "2") (pinfunction "2_2") (pintype "passive"))
      (node (ref "R49") (pin "1") (pinfunction "1_1") (pintype "passive"))
      (node (ref "R50") (pin "2") (pinfunction "2_2") (pintype "passive"))
      (node (ref "R51") (pin "2") (pinfunction "2_2") (pintype "passive"))
      (node (ref "R52") (pin "2") (pinfunction "2_2") (pintype "passive"))
      (node (ref "U8") (pin "1") (pinfunction "GND_1") (pintype "power_in"))
    )
    (net (code "69") (name "Net-(Q201-G)") (class "Default")
      (node (ref "Q201") (pin "3") (pinfunction "G_3") (pintype "passive"))
      (node (ref "R48") (pin "1") (pinfunction "1_1") (pintype "passive"))
      (node (ref "R49") (pin "2") (pinfunction "2_2") (pintype "passive"))
    )
    (net (code "70") (name "Net-(R31-Pad2)") (class "Default")
      (node (ref "R31") (pin "2") (pinfunction "2_2") (pintype "passive"))
      (node (ref "R43") (pin "1") (pinfunction "1_1") (pintype "passive"))
    )
    (net (code "71") (name "Net-(U1A-VINA+)") (class "Default")
      (node (ref "R3") (pin "1") (pinfunction "1_1") (pintype "passive"))
      (node (ref "R4") (pin "1") (pinfunction "1_1") (pintype "passive"))
      (node (ref "U1") (pin "3") (pinfunction "VINA+_3") (pintype "input"))
      (node (ref "VD1") (pin "1") (pinfunction "ANODE_1") (pintype "passive"))
    )
    (net (code "72") (name "Net-(U1A-VINA-)") (class "Default")
      (node (ref "C7") (pin "1") (pinfunction "1_1") (pintype "passive"))
      (node (ref "R5") (pin "1") (pinfunction "1_1") (pintype "passive"))
      (node (ref "R6") (pin "1") (pinfunction "1_1") (pintype "passive"))
      (node (ref "R9") (pin "2") (pinfunction "2_2") (pintype "passive"))
      (node (ref "U1") (pin "2") (pinfunction "VINA-_2") (pintype "input"))
    )
    (net (code "73") (name "Net-(U1A-VOUTA)") (class "Default")
      (node (ref "C7") (pin "2") (pinfunction "2_2") (pintype "passive"))
      (node (ref "R13") (pin "1") (pinfunction "1_1") (pintype "passive"))
      (node (ref "R9") (pin "1") (pinfunction "1_1") (pintype "passive"))
      (node (ref "U1") (pin "1") (pinfunction "VOUTA_1") (pintype "output"))
    )
    (net (code "74") (name "Net-(U1B-VINB+)") (class "Default")
      (node (ref "C16") (pin "1") (pinfunction "1_1") (pintype "passive"))
      (node (ref "R18") (pin "2") (pinfunction "2_2") (pintype "passive"))
      (node (ref "R19") (pin "1") (pinfunction "1_1") (pintype "passive"))
      (node (ref "U1") (pin "5") (pinfunction "VINB+_5") (pintype "input"))
    )
    (net (code "75") (name "Net-(U2A-PB2)") (class "Default")
      (node (ref "R16") (pin "2") (pinfunction "2_2") (pintype "passive"))
      (node (ref "U2") (pin "20") (pinfunction "PB2_20") (pintype "bidirectional"))
    )
    (net (code "76") (name "Net-(U2A-PD0-OSC_IN)") (class "Default")
      (node (ref "BQ1") (pin "1") (pinfunction "1_1") (pintype "passive"))
      (node (ref "C10") (pin "2") (pinfunction "2_2") (pintype "passive"))
      (node (ref "U2") (pin "5") (pinfunction "PD0-OSC_IN_5") (pintype "bidirectional"))
    )
    (net (code "77") (name "Net-(U2A-PD1)") (class "Default")
      (node (ref "R15") (pin "1") (pinfunction "1_1") (pintype "passive"))
      (node (ref "U2") (pin "6") (pinfunction "PD1_6") (pintype "bidirectional"))
    )
    (net (code "78") (name "Net-(U4-A2)") (class "Default")
      (node (ref "R40") (pin "1") (pinfunction "1_1") (pintype "passive"))
      (node (ref "U4") (pin "3") (pinfunction "A2_3") (pintype "input"))
    )
    (net (code "79") (name "Net-(U7-FC1)") (class "Default")
      (node (ref "C30") (pin "2") (pinfunction "2_2") (pintype "passive"))
      (node (ref "U7") (pin "3") (pinfunction "FC1_3") (pintype "passive"))
    )
    (net (code "80") (name "Net-(U7-VIN)") (class "Default")
      (node (ref "C32") (pin "1") (pinfunction "1_1") (pintype "passive"))
      (node (ref "R29") (pin "1") (pinfunction "1_1") (pintype "passive"))
      (node (ref "R32") (pin "2") (pinfunction "2_2") (pintype "passive"))
      (node (ref "U7") (pin "4") (pinfunction "VIN_4") (pintype "input"))
    )
    (net (code "81") (name "Net-(U7-VO1)") (class "Default")
      (node (ref "C32") (pin "2") (pinfunction "2_2") (pintype "passive"))
      (node (ref "R32") (pin "1") (pinfunction "1_1") (pintype "passive"))
      (node (ref "R38") (pin "1") (pinfunction "1_1") (pintype "passive"))
      (node (ref "U7") (pin "5") (pinfunction "VO1_5") (pintype "output"))
    )
    (net (code "82") (name "Net-(U7-VO2)") (class "Default")
      (node (ref "R39") (pin "1") (pinfunction "1_1") (pintype "passive"))
      (node (ref "U7") (pin "8") (pinfunction "VO2_8") (pintype "output"))
    )
    (net (code "83") (name "Net-(VD2-CATODE1)") (class "Default")
      (node (ref "Q1") (pin "5") (pinfunction "D2_5") (pintype "passive"))
      (node (ref "Q1") (pin "6") (pinfunction "D2_6") (pintype "passive"))
      (node (ref "Q1") (pin "7") (pinfunction "D1_7") (pintype "passive"))
      (node (ref "Q1") (pin "8") (pinfunction "D1_8") (pintype "passive"))
      (node (ref "R2") (pin "2") (pinfunction "2_2") (pintype "passive"))
      (node (ref "VD2") (pin "2") (pinfunction "CATODE1_2") (pintype "passive"))
      (node (ref "VD3") (pin "1") (pinfunction "ANODE_1") (pintype "passive"))
    )
    (net (code "84") (name "Net-(VD8-ANODE)") (class "Default")
      (node (ref "R41") (pin "1") (pinfunction "1_1") (pintype "passive"))
      (node (ref "VD8") (pin "2") (pinfunction "ANODE_2") (pintype "passive"))
    )
    (net (code "85") (name "Net-(VD9-ANODE)") (class "Default")
      (node (ref "R55") (pin "1") (pinfunction "1_1") (pintype "passive"))
      (node (ref "VD9") (pin "2") (pinfunction "ANODE_2") (pintype "passive"))
    )
    (net (code "86") (name "Net-(VD10-ANODE)") (class "Default")
      (node (ref "R53") (pin "1") (pinfunction "1_1") (pintype "passive"))
      (node (ref "VD10") (pin "2") (pinfunction "ANODE_2") (pintype "passive"))
    )
    (net (code "87") (name "Net-(VD11-ANODE)") (class "Default")
      (node (ref "R54") (pin "1") (pinfunction "1_1") (pintype "passive"))
      (node (ref "VD11") (pin "2") (pinfunction "ANODE_2") (pintype "passive"))
    )
    (net (code "88") (name "Net-(VD12-ANODE)") (class "Default")
      (node (ref "R58") (pin "2") (pinfunction "2_2") (pintype "passive"))
      (node (ref "VD12") (pin "2") (pinfunction "ANODE_2") (pintype "passive"))
    )
    (net (code "89") (name "Net-(VD13-ANODE)") (class "Default")
      (node (ref "R57") (pin "2") (pinfunction "2_2") (pintype "passive"))
      (node (ref "VD13") (pin "2") (pinfunction "ANODE_2") (pintype "passive"))
    )
    (net (code "90") (name "Net-(VD14-ANODE)") (class "Default")
      (node (ref "R56") (pin "2") (pinfunction "2_2") (pintype "passive"))
      (node (ref "VD14") (pin "2") (pinfunction "ANODE_2") (pintype "passive"))
    )
    (net (code "91") (name "Net-(VD15-ANODE)") (class "Default")
      (node (ref "R59") (pin "2") (pinfunction "2_2") (pintype "passive"))
      (node (ref "VD15") (pin "2") (pinfunction "ANODE_2") (pintype "passive"))
    )
    (net (code "92") (name "Net-(X1-SWCLK)") (class "Default")
      (node (ref "R36") (pin "1") (pinfunction "1_1") (pintype "passive"))
      (node (ref "X1") (pin "2") (pinfunction "SWCLK_2") (pintype "passive"))
    )
    (net (code "93") (name "Net-(X1-SWDIO)") (class "Default")
      (node (ref "R37") (pin "1") (pinfunction "1_1") (pintype "passive"))
      (node (ref "X1") (pin "4") (pinfunction "SWDIO_4") (pintype "passive"))
    )
    (net (code "94") (name "Net-(X2-GND)") (class "Default")
      (node (ref "R33") (pin "2") (pinfunction "2_2") (pintype "passive"))
      (node (ref "X2") (pin "3") (pinfunction "GND_3") (pintype "passive"))
    )
    (net (code "95") (name "Net-(X2-SWDIO)") (class "Default")
      (node (ref "R34") (pin "1") (pinfunction "1_1") (pintype "passive"))
      (node (ref "X2") (pin "4") (pinfunction "SWDIO_4") (pintype "passive"))
    )
    (net (code "96") (name "Net-(X4-GND)") (class "Default")
      (node (ref "R39") (pin "2") (pinfunction "2_2") (pintype "passive"))
      (node (ref "X4") (pin "2") (pinfunction "GND_2") (pintype "passive"))
    )
    (net (code "97") (name "Net-(X5-RX)") (class "Default")
      (node (ref "C1") (pin "2") (pinfunction "2_2") (pintype "passive"))
      (node (ref "X5") (pin "1") (pinfunction "RX_1") (pintype "passive"))
    )
    (net (code "98") (name "Net-(X6-RX)") (class "Default")
      (node (ref "R2") (pin "1") (pinfunction "1_1") (pintype "passive"))
      (node (ref "X6") (pin "1") (pinfunction "RX_1") (pintype "passive"))
    )
    (net (code "99") (name "Net-(X7-RX)") (class "Default")
      (node (ref "X10") (pin "1") (pinfunction "1_1") (pintype "passive"))
      (node (ref "X7") (pin "1") (pinfunction "RX_1") (pintype "passive"))
    )
    (net (code "100") (name "Net-(X8-A)") (class "Default")
      (node (ref "R31") (pin "1") (pinfunction "1_1") (pintype "passive"))
      (node (ref "X8") (pin "15") (pinfunction "A_15") (pintype "passive"))
    )
    (net (code "101") (name "Net-(X8-CNTRST)") (class "Default")
      (node (ref "R27") (pin "1") (pinfunction "1_1") (pintype "passive"))
      (node (ref "X8") (pin "3") (pinfunction "CNTRST_3") (pintype "passive"))
    )
    (net (code "102") (name "VDDA_3V3") (class "Default")
      (node (ref "C15") (pin "2") (pinfunction "2_2") (pintype "passive"))
      (node (ref "C18") (pin "1") (pinfunction "1_1") (pintype "passive"))
      (node (ref "C20") (pin "2") (pinfunction "2_2") (pintype "passive"))
      (node (ref "C28") (pin "1") (pinfunction "1_1") (pintype "passive"))
      (node (ref "R18") (pin "1") (pinfunction "1_1") (pintype "passive"))
      (node (ref "U1") (pin "8") (pinfunction "VDD_8") (pintype "power_in"))
      (node (ref "U2") (pin "9") (pinfunction "VDDA_9") (pintype "power_in"))
      (node (ref "U5") (pin "2") (pinfunction "VOUT_2") (pintype "power_in"))
      (node (ref "U5") (pin "4") (pinfunction "VOUT_4") (pintype "power_in"))
      (node (ref "VD1") (pin "2") (pinfunction "CATODE1_2") (pintype "passive"))
    )
    (net (code "103") (name "VDD_3V3") (class "Default")
      (node (ref "C13") (pin "1") (pinfunction "1_1") (pintype "passive"))
      (node (ref "C21") (pin "1") (pinfunction "1_1") (pintype "passive"))
      (node (ref "C22") (pin "1") (pinfunction "1_1") (pintype "passive"))
      (node (ref "C24") (pin "1") (pinfunction "1_1") (pintype "passive"))
      (node (ref "C25") (pin "1") (pinfunction "1_1") (pintype "passive"))
      (node (ref "C26") (pin "1") (pinfunction "1_1") (pintype "passive"))
      (node (ref "C27") (pin "1") (pinfunction "1_1") (pintype "passive"))
      (node (ref "C29") (pin "1") (pinfunction "1_1") (pintype "passive"))
      (node (ref "C35") (pin "1") (pinfunction "1_1") (pintype "passive"))
      (node (ref "DD1") (pin "1") (pinfunction "A0_1") (pintype "passive"))
      (node (ref "DD1") (pin "16") (pinfunction "VCC_16") (pintype "passive"))
      (node (ref "DD1") (pin "2") (pinfunction "A1_2") (pintype "passive"))
      (node (ref "DD1") (pin "3") (pinfunction "A2_3") (pintype "passive"))
      (node (ref "P1") (pin "3") (pinfunction "3_3") (pintype "passive"))
      (node (ref "R22") (pin "2") (pinfunction "2_2") (pintype "passive"))
      (node (ref "R23") (pin "2") (pinfunction "2_2") (pintype "passive"))
      (node (ref "R44") (pin "2") (pinfunction "2_2") (pintype "passive"))
      (node (ref "U2") (pin "1") (pinfunction "VBAT_1") (pintype "power_in"))
      (node (ref "U2") (pin "24") (pinfunction "VDD_1_24") (pintype "power_in"))
      (node (ref "U2") (pin "36") (pinfunction "VDD_2_36") (pintype "power_in"))
      (node (ref "U2") (pin "48") (pinfunction "VDD_3_48") (pintype "power_in"))
      (node (ref "U3") (pin "2") (pinfunction "VOUT_2") (pintype "power_in"))
      (node (ref "U3") (pin "4") (pinfunction "VOUT_4") (pintype "power_in"))
      (node (ref "U4") (pin "8") (pinfunction "VCC_8") (pintype "power_in"))
      (node (ref "VD16") (pin "2") (pinfunction "CATODE1_2") (pintype "passive"))
      (node (ref "X1") (pin "1") (pinfunction "VDD_1") (pintype "passive"))
      (node (ref "X2") (pin "1") (pinfunction "VDD_1") (pintype "passive"))
      (node (ref "XP1") (pin "1") (pinfunction "1_1") (pintype "passive"))
    )
    (net (code "104") (name "VDD_5V_TX") (class "Default")
      (node (ref "C3") (pin "1") (pinfunction "1_1") (pintype "passive"))
      (node (ref "C37") (pin "1") (pinfunction "1_1") (pintype "passive"))
      (node (ref "C4") (pin "1") (pinfunction "1_1") (pintype "passive"))
      (node (ref "C52") (pin "1") (pinfunction "1_1") (pintype "passive"))
      (node (ref "C6") (pin "2") (pinfunction "2_2") (pintype "passive"))
      (node (ref "Q1") (pin "1") (pinfunction "S1_1") (pintype "passive"))
      (node (ref "Q2") (pin "3") (pinfunction "C_3") (pintype "passive"))
      (node (ref "R12") (pin "1") (pinfunction "1_1") (pintype "passive"))
      (node (ref "R14") (pin "1") (pinfunction "1_1") (pintype "passive"))
      (node (ref "R50") (pin "1") (pinfunction "1_1") (pintype "passive"))
      (node (ref "R51") (pin "1") (pinfunction "1_1") (pintype "passive"))
      (node (ref "R52") (pin "1") (pinfunction "1_1") (pintype "passive"))
      (node (ref "U8") (pin "2") (pinfunction "VOUT_2") (pintype "power_in"))
      (node (ref "U8") (pin "4") (pinfunction "VOUT_4") (pintype "power_in"))
      (node (ref "VD3") (pin "2") (pinfunction "CATODE1_2") (pintype "passive"))
    )
    (net (code "105") (name "unconnected-(DD1-~{INT}-Pad13)") (class "Default")
      (node (ref "DD1") (pin "13") (pinfunction "~{INT}_13") (pintype "passive+no_connect"))
    )
    (net (code "106") (name "unconnected-(P1-Pad1)") (class "Default")
      (node (ref "P1") (pin "1") (pinfunction "1_1") (pintype "passive+no_connect"))
    )
    (net (code "107") (name "unconnected-(U2A-PA0-WKUP-Pad10)") (class "Default")
      (node (ref "U2") (pin "10") (pinfunction "PA0-WKUP_10") (pintype "bidirectional+no_connect"))
    )
    (net (code "108") (name "unconnected-(U2A-PA6-Pad16)") (class "Default")
      (node (ref "U2") (pin "16") (pinfunction "PA6_16") (pintype "bidirectional+no_connect"))
    )
    (net (code "109") (name "unconnected-(U2A-PA11-Pad32)") (class "Default")
      (node (ref "U2") (pin "32") (pinfunction "PA11_32") (pintype "bidirectional+no_connect"))
    )
    (net (code "110") (name "unconnected-(U2A-PB0-Pad18)") (class "Default")
      (node (ref "U2") (pin "18") (pinfunction "PB0_18") (pintype "bidirectional+no_connect"))
    )
    (net (code "111") (name "unconnected-(U2A-PC15-OSC32_OUT-Pad4)") (class "Default")
      (node (ref "U2") (pin "4") (pinfunction "PC15-OSC32_OUT_4") (pintype "bidirectional+no_connect"))
    )
    (net (code "112") (name "unconnected-(U4-NC-Pad1)") (class "Default")
      (node (ref "U4") (pin "1") (pinfunction "NC_1") (pintype "passive+no_connect"))
    )
    (net (code "113") (name "unconnected-(U4-NC-Pad2)") (class "Default")
      (node (ref "U4") (pin "2") (pinfunction "NC_2") (pintype "passive+no_connect"))
    )
    (net (code "114") (name "unconnected-(U7-FC2-Pad2)") (class "Default")
      (node (ref "U7") (pin "2") (pinfunction "FC2_2") (pintype "passive+no_connect"))
    )
    (net (code "115") (name "unconnected-(X8-DB0-Pad7)") (class "Default")
      (node (ref "X8") (pin "7") (pinfunction "DB0_7") (pintype "passive+no_connect"))
    )
    (net (code "116") (name "unconnected-(X8-DB1-Pad8)") (class "Default")
      (node (ref "X8") (pin "8") (pinfunction "DB1_8") (pintype "passive+no_connect"))
    )
    (net (code "117") (name "unconnected-(X8-DB2-Pad9)") (class "Default")
      (node (ref "X8") (pin "9") (pinfunction "DB2_9") (pintype "passive+no_connect"))
    )
    (net (code "118") (name "unconnected-(X8-DB3-Pad10)") (class "Default")
      (node (ref "X8") (pin "10") (pinfunction "DB3_10") (pintype "passive+no_connect"))
    )
  )
)
